# Buck_V1.net
KiCad netlist of a schematic drawn in EAGLE
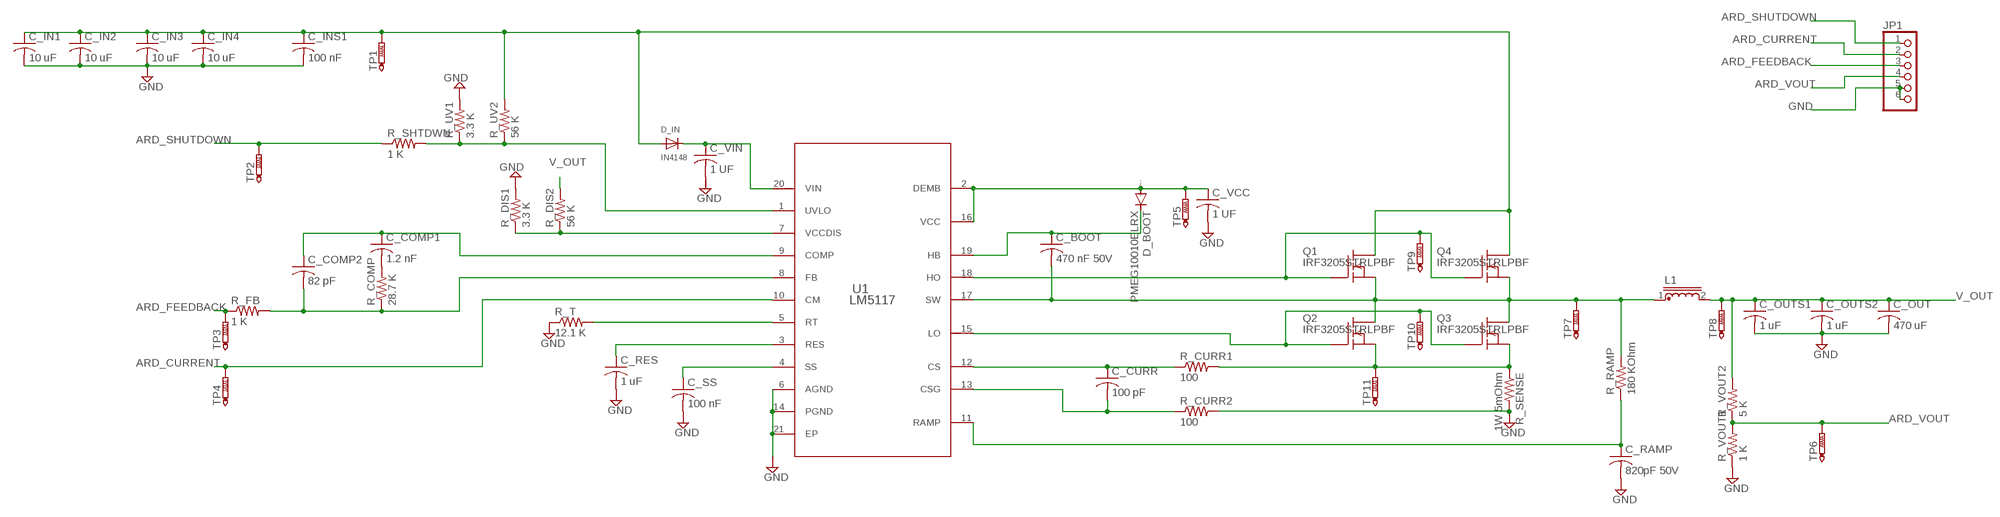
[diagram p0: schematic, sheet 1]

(export (version "E")
  (design (tool "Eeschema 10.0.6"))
  (components
    (comp (ref "C_BOOT")
      (value "470 nF 50V")
      (footprint "eagle-import:C0603")
      (libsource (lib "eagle-import") (part "rcl_334_C-USC0603"))
    )
    (comp (ref "C_COMP1")
      (value "1.2 nF")
      (footprint "eagle-import:C0603")
      (libsource (lib "eagle-import") (part "C-USC0603"))
    )
    (comp (ref "C_COMP2")
      (value "82 pF")
      (footprint "eagle-import:C0603")
      (libsource (lib "eagle-import") (part "C-USC0603"))
    )
    (comp (ref "C_CURR")
      (value "100 pF")
      (footprint "eagle-import:C0603")
      (libsource (lib "eagle-import") (part "C-USC0603"))
    )
    (comp (ref "C_IN1")
      (value "10 uF")
      (footprint "eagle-import:C1206")
      (libsource (lib "eagle-import") (part "C-USC1206"))
    )
    (comp (ref "C_IN2")
      (value "10 uF")
      (footprint "eagle-import:C1206")
      (libsource (lib "eagle-import") (part "C-USC1206"))
    )
    (comp (ref "C_IN3")
      (value "10 uF")
      (footprint "eagle-import:C1206")
      (libsource (lib "eagle-import") (part "C-USC1206"))
    )
    (comp (ref "C_IN4")
      (value "10 uF")
      (footprint "eagle-import:C1206")
      (fields (field (name "SPICEPREFIX") "C"))
      (libsource (lib "eagle-import") (part "C-USC1206"))
    )
    (comp (ref "C_INS1")
      (value "100 nF")
      (footprint "eagle-import:C0603")
      (libsource (lib "eagle-import") (part "C-USC0603"))
    )
    (comp (ref "C_OUT")
      (value "470 uF")
      (footprint "eagle-import:CAP_PANASONIC_H13")
      (libsource (lib "eagle-import") (part "CAP_PANASONIC_H13"))
    )
    (comp (ref "C_OUTS1")
      (value "1 uF")
      (footprint "eagle-import:C0805")
      (libsource (lib "eagle-import") (part "rcl_334_C-USC0805"))
    )
    (comp (ref "C_OUTS2")
      (value "1 uF")
      (footprint "eagle-import:C0805")
      (libsource (lib "eagle-import") (part "rcl_334_C-USC0805"))
    )
    (comp (ref "C_RAMP")
      (value "820pF 50V")
      (footprint "eagle-import:C0603")
      (libsource (lib "eagle-import") (part "rcl_334_C-USC0603"))
    )
    (comp (ref "C_RES")
      (value "1 uF")
      (footprint "eagle-import:C0603")
      (libsource (lib "eagle-import") (part "C-USC0603"))
    )
    (comp (ref "C_SS")
      (value "100 nF")
      (footprint "eagle-import:C0603")
      (libsource (lib "eagle-import") (part "C-USC0603"))
    )
    (comp (ref "C_VCC")
      (value "1 UF")
      (footprint "eagle-import:C0603")
      (libsource (lib "eagle-import") (part "rcl_334_C-USC0603"))
    )
    (comp (ref "C_VIN")
      (value "1 UF")
      (footprint "eagle-import:C0603")
      (libsource (lib "eagle-import") (part "rcl_334_C-USC0603"))
    )
    (comp (ref "D_BOOT")
      (value "PMEG10010ELRX")
      (footprint "eagle-import:SOD123")
      (libsource (lib "eagle-import") (part "DIODE-SOD123"))
    )
    (comp (ref "D_IN")
      (value "IN4148")
      (footprint "eagle-import:SOD-123")
      (libsource (lib "eagle-import") (part "DIODESOD-123"))
    )
    (comp (ref "JP1")
      (value "PINHD-1X6")
      (footprint "eagle-import:1X06")
      (libsource (lib "eagle-import") (part "PINHD-1X6"))
    )
    (comp (ref "L1")
      (value "17.5X17.5_INDUCTOR_SMD")
      (footprint "eagle-import:17.5X17.5_INDUCTOR_SMD")
      (libsource (lib "eagle-import") (part "17.5X17.5_INDUCTOR_SMD"))
    )
    (comp (ref "Q1")
      (value "IRF3205STRLPBF")
      (footprint "eagle-import:D2PAK")
      (libsource (lib "eagle-import") (part "IRF510D2PAK"))
    )
    (comp (ref "Q2")
      (value "IRF3205STRLPBF")
      (footprint "eagle-import:D2PAK")
      (libsource (lib "eagle-import") (part "IRF510D2PAK"))
    )
    (comp (ref "Q3")
      (value "IRF3205STRLPBF")
      (footprint "eagle-import:D2PAK")
      (libsource (lib "eagle-import") (part "IRF510D2PAK"))
    )
    (comp (ref "Q4")
      (value "IRF3205STRLPBF")
      (footprint "eagle-import:D2PAK")
      (libsource (lib "eagle-import") (part "IRF510D2PAK"))
    )
    (comp (ref "R_COMP")
      (value "28.7 K")
      (footprint "eagle-import:R0603")
      (libsource (lib "eagle-import") (part "R-US_R0603"))
    )
    (comp (ref "R_CURR1")
      (value "100")
      (footprint "eagle-import:R0603")
      (libsource (lib "eagle-import") (part "R-US_R0603"))
    )
    (comp (ref "R_CURR2")
      (value "100")
      (footprint "eagle-import:R0603")
      (libsource (lib "eagle-import") (part "R-US_R0603"))
    )
    (comp (ref "R_DIS1")
      (value "3.3 K")
      (footprint "eagle-import:R0603")
      (libsource (lib "eagle-import") (part "R-US_R0603"))
    )
    (comp (ref "R_DIS2")
      (value "56 K")
      (footprint "eagle-import:R0603")
      (libsource (lib "eagle-import") (part "R-US_R0603"))
    )
    (comp (ref "R_FB")
      (value "1 K")
      (footprint "eagle-import:R0603")
      (libsource (lib "eagle-import") (part "R-US_R0603"))
    )
    (comp (ref "R_RAMP")
      (value "180 KOhm")
      (footprint "eagle-import:R0603")
      (libsource (lib "eagle-import") (part "rcl_334_R-US_R0603"))
    )
    (comp (ref "R_SENSE")
      (value "1W 5mOhm")
      (footprint "eagle-import:R2512")
      (libsource (lib "eagle-import") (part "rcl_334_R-US_R2512"))
    )
    (comp (ref "R_SHTDWN")
      (value "1 K")
      (footprint "eagle-import:R0603")
      (libsource (lib "eagle-import") (part "R-US_R0603"))
    )
    (comp (ref "R_T")
      (value "12.1 K")
      (footprint "eagle-import:R0603")
      (libsource (lib "eagle-import") (part "R-US_R0603"))
    )
    (comp (ref "R_UV1")
      (value "3.3 K")
      (footprint "eagle-import:R0603")
      (libsource (lib "eagle-import") (part "R-US_R0603"))
    )
    (comp (ref "R_UV2")
      (value "56 K")
      (footprint "eagle-import:R0603")
      (libsource (lib "eagle-import") (part "R-US_R0603"))
    )
    (comp (ref "R_VOUT1")
      (value "1 K")
      (footprint "eagle-import:R0603")
      (libsource (lib "eagle-import") (part "R-US_R0603"))
    )
    (comp (ref "R_VOUT2")
      (value "5 K")
      (footprint "eagle-import:R0603")
      (libsource (lib "eagle-import") (part "R-US_R0603"))
    )
    (comp (ref "TP1")
      (value "PTR1TP20R")
      (footprint "eagle-import:TP20R")
      (libsource (lib "eagle-import") (part "PTR1TP20R"))
    )
    (comp (ref "TP2")
      (value "PTR1TP20R")
      (footprint "eagle-import:TP20R")
      (libsource (lib "eagle-import") (part "PTR1TP20R"))
    )
    (comp (ref "TP3")
      (value "PTR1TP20R")
      (footprint "eagle-import:TP20R")
      (libsource (lib "eagle-import") (part "PTR1TP20R"))
    )
    (comp (ref "TP4")
      (value "PTR1TP20R")
      (footprint "eagle-import:TP20R")
      (libsource (lib "eagle-import") (part "PTR1TP20R"))
    )
    (comp (ref "TP5")
      (value "PTR1TP20R")
      (footprint "eagle-import:TP20R")
      (libsource (lib "eagle-import") (part "PTR1TP20R"))
    )
    (comp (ref "TP6")
      (value "PTR1TP20R")
      (footprint "eagle-import:TP20R")
      (libsource (lib "eagle-import") (part "PTR1TP20R"))
    )
    (comp (ref "TP7")
      (value "PTR1TP20R")
      (footprint "eagle-import:TP20R")
      (libsource (lib "eagle-import") (part "PTR1TP20R"))
    )
    (comp (ref "TP8")
      (value "PTR1TP20R")
      (footprint "eagle-import:TP20R")
      (libsource (lib "eagle-import") (part "PTR1TP20R"))
    )
    (comp (ref "TP9")
      (value "PTR1TP20R")
      (footprint "eagle-import:TP20R")
      (libsource (lib "eagle-import") (part "PTR1TP20R"))
    )
    (comp (ref "TP10")
      (value "PTR1TP20R")
      (footprint "eagle-import:TP20R")
      (libsource (lib "eagle-import") (part "PTR1TP20R"))
    )
    (comp (ref "TP11")
      (value "PTR1TP20R")
      (footprint "eagle-import:TP20R")
      (libsource (lib "eagle-import") (part "PTR1TP20R"))
    )
    (comp (ref "U1")
      (value "LM5117")
      (footprint "eagle-import:PWP0020A")
      (fields (field (name "MANUFACTURER") "Texas Instruments") (field (name "PARTNUMBER") "LM5117PMHXNOPB"))
      (libsource (lib "eagle-import") (part "LM5117PMHX/NOPB"))
    )
  )
  (nets
    (net (code "1") (name "/ARD_CURRENT") (class "Default")
      (node (ref "JP1") (pin "2") (pinfunction "2_2") (pintype "passive"))
      (node (ref "TP4") (pin "TP") (pinfunction "TP_TP") (pintype "input"))
      (node (ref "U1") (pin "10") (pinfunction "CM_10") (pintype "output"))
    )
    (net (code "2") (name "/ARD_FEEDBACK") (class "Default")
      (node (ref "JP1") (pin "3") (pinfunction "3_3") (pintype "passive"))
      (node (ref "R_FB") (pin "1") (pinfunction "1_1") (pintype "passive"))
      (node (ref "TP3") (pin "TP") (pinfunction "TP_TP") (pintype "input"))
    )
    (net (code "3") (name "/ARD_SHUTDOWN") (class "Default")
      (node (ref "JP1") (pin "1") (pinfunction "1_1") (pintype "passive"))
      (node (ref "R_SHTDWN") (pin "1") (pinfunction "1_1") (pintype "passive"))
      (node (ref "TP2") (pin "TP") (pinfunction "TP_TP") (pintype "input"))
    )
    (net (code "4") (name "/ARD_VOUT") (class "Default")
      (node (ref "JP1") (pin "4") (pinfunction "4_4") (pintype "passive"))
      (node (ref "R_VOUT1") (pin "2") (pinfunction "2_2") (pintype "passive"))
      (node (ref "R_VOUT2") (pin "1") (pinfunction "1_1") (pintype "passive"))
      (node (ref "TP6") (pin "TP") (pinfunction "TP_TP") (pintype "input"))
    )
    (net (code "5") (name "/V_OUT") (class "Default")
      (node (ref "C_OUT") (pin "P$2") (pinfunction "2_P$2") (pintype "passive"))
      (node (ref "C_OUTS1") (pin "1") (pinfunction "1_1") (pintype "passive"))
      (node (ref "C_OUTS2") (pin "1") (pinfunction "1_1") (pintype "passive"))
      (node (ref "L1") (pin "2") (pinfunction "2_2") (pintype "passive"))
      (node (ref "R_DIS2") (pin "2") (pinfunction "2_2") (pintype "passive"))
      (node (ref "R_VOUT2") (pin "2") (pinfunction "2_2") (pintype "passive"))
      (node (ref "TP8") (pin "TP") (pinfunction "TP_TP") (pintype "input"))
    )
    (net (code "6") (name "GND") (class "Default")
      (node (ref "C_IN1") (pin "2") (pinfunction "2_2") (pintype "passive"))
      (node (ref "C_IN2") (pin "2") (pinfunction "2_2") (pintype "passive"))
      (node (ref "C_IN3") (pin "2") (pinfunction "2_2") (pintype "passive"))
      (node (ref "C_IN4") (pin "2") (pinfunction "2_2") (pintype "passive"))
      (node (ref "C_INS1") (pin "2") (pinfunction "2_2") (pintype "passive"))
      (node (ref "C_OUT") (pin "P$1") (pinfunction "1_P$1") (pintype "passive"))
      (node (ref "C_OUTS1") (pin "2") (pinfunction "2_2") (pintype "passive"))
      (node (ref "C_OUTS2") (pin "2") (pinfunction "2_2") (pintype "passive"))
      (node (ref "C_RAMP") (pin "2") (pinfunction "2_2") (pintype "passive"))
      (node (ref "C_RES") (pin "2") (pinfunction "2_2") (pintype "passive"))
      (node (ref "C_SS") (pin "2") (pinfunction "2_2") (pintype "passive"))
      (node (ref "C_VCC") (pin "2") (pinfunction "2_2") (pintype "passive"))
      (node (ref "C_VIN") (pin "2") (pinfunction "2_2") (pintype "passive"))
      (node (ref "JP1") (pin "5") (pinfunction "5_5") (pintype "passive"))
      (node (ref "JP1") (pin "6") (pinfunction "6_6") (pintype "passive"))
      (node (ref "R_CURR2") (pin "2") (pinfunction "2_2") (pintype "passive"))
      (node (ref "R_DIS1") (pin "2") (pinfunction "2_2") (pintype "passive"))
      (node (ref "R_SENSE") (pin "2") (pinfunction "2_2") (pintype "passive"))
      (node (ref "R_T") (pin "1") (pinfunction "1_1") (pintype "passive"))
      (node (ref "R_UV1") (pin "2") (pinfunction "2_2") (pintype "passive"))
      (node (ref "R_VOUT1") (pin "1") (pinfunction "1_1") (pintype "passive"))
      (node (ref "U1") (pin "14") (pinfunction "PGND_14") (pintype "power_in"))
      (node (ref "U1") (pin "21") (pinfunction "EP_21") (pintype "passive"))
      (node (ref "U1") (pin "6") (pinfunction "AGND_6") (pintype "power_in"))
    )
    (net (code "7") (name "Net-(C_COMP1-Pad2)") (class "Default")
      (node (ref "C_COMP1") (pin "2") (pinfunction "2_2") (pintype "passive"))
      (node (ref "R_COMP") (pin "2") (pinfunction "2_2") (pintype "passive"))
    )
    (net (code "8") (name "Net-(Q1-D)") (class "Default")
      (node (ref "C_IN1") (pin "1") (pinfunction "1_1") (pintype "passive"))
      (node (ref "C_IN2") (pin "1") (pinfunction "1_1") (pintype "passive"))
      (node (ref "C_IN3") (pin "1") (pinfunction "1_1") (pintype "passive"))
      (node (ref "C_IN4") (pin "1") (pinfunction "1_1") (pintype "passive"))
      (node (ref "C_INS1") (pin "1") (pinfunction "1_1") (pintype "passive"))
      (node (ref "D_IN") (pin "A") (pinfunction "A_A") (pintype "passive"))
      (node (ref "Q1") (pin "2") (pinfunction "D_2") (pintype "passive"))
      (node (ref "Q4") (pin "2") (pinfunction "D_2") (pintype "passive"))
      (node (ref "R_UV2") (pin "2") (pinfunction "2_2") (pintype "passive"))
      (node (ref "TP1") (pin "TP") (pinfunction "TP_TP") (pintype "input"))
    )
    (net (code "9") (name "Net-(Q1-G)") (class "Default")
      (node (ref "Q1") (pin "1") (pinfunction "G_1") (pintype "passive"))
      (node (ref "Q4") (pin "1") (pinfunction "G_1") (pintype "passive"))
      (node (ref "TP9") (pin "TP") (pinfunction "TP_TP") (pintype "input"))
      (node (ref "U1") (pin "18") (pinfunction "HO_18") (pintype "output"))
    )
    (net (code "10") (name "Net-(Q1-S)") (class "Default")
      (node (ref "C_BOOT") (pin "2") (pinfunction "2_2") (pintype "passive"))
      (node (ref "L1") (pin "1") (pinfunction "1_1") (pintype "passive"))
      (node (ref "Q1") (pin "3") (pinfunction "S_3") (pintype "passive"))
      (node (ref "Q2") (pin "2") (pinfunction "D_2") (pintype "passive"))
      (node (ref "Q3") (pin "2") (pinfunction "D_2") (pintype "passive"))
      (node (ref "Q4") (pin "3") (pinfunction "S_3") (pintype "passive"))
      (node (ref "R_RAMP") (pin "2") (pinfunction "2_2") (pintype "passive"))
      (node (ref "TP7") (pin "TP") (pinfunction "TP_TP") (pintype "input"))
      (node (ref "U1") (pin "17") (pinfunction "SW_17") (pintype "power_in"))
    )
    (net (code "11") (name "Net-(Q2-G)") (class "Default")
      (node (ref "Q2") (pin "1") (pinfunction "G_1") (pintype "passive"))
      (node (ref "Q3") (pin "1") (pinfunction "G_1") (pintype "passive"))
      (node (ref "TP10") (pin "TP") (pinfunction "TP_TP") (pintype "input"))
      (node (ref "U1") (pin "15") (pinfunction "LO_15") (pintype "output"))
    )
    (net (code "12") (name "Net-(Q2-S)") (class "Default")
      (node (ref "Q2") (pin "3") (pinfunction "S_3") (pintype "passive"))
      (node (ref "Q3") (pin "3") (pinfunction "S_3") (pintype "passive"))
      (node (ref "R_CURR1") (pin "2") (pinfunction "2_2") (pintype "passive"))
      (node (ref "R_SENSE") (pin "1") (pinfunction "1_1") (pintype "passive"))
      (node (ref "TP11") (pin "TP") (pinfunction "TP_TP") (pintype "input"))
    )
    (net (code "13") (name "Net-(U1-COMP)") (class "Default")
      (node (ref "C_COMP1") (pin "1") (pinfunction "1_1") (pintype "passive"))
      (node (ref "C_COMP2") (pin "1") (pinfunction "1_1") (pintype "passive"))
      (node (ref "U1") (pin "9") (pinfunction "COMP_9") (pintype "output"))
    )
    (net (code "14") (name "Net-(U1-CS)") (class "Default")
      (node (ref "C_CURR") (pin "1") (pinfunction "1_1") (pintype "passive"))
      (node (ref "R_CURR1") (pin "1") (pinfunction "1_1") (pintype "passive"))
      (node (ref "U1") (pin "12") (pinfunction "CS_12") (pintype "input"))
    )
    (net (code "15") (name "Net-(U1-CSG)") (class "Default")
      (node (ref "C_CURR") (pin "2") (pinfunction "2_2") (pintype "passive"))
      (node (ref "R_CURR2") (pin "1") (pinfunction "1_1") (pintype "passive"))
      (node (ref "U1") (pin "13") (pinfunction "CSG_13") (pintype "input"))
    )
    (net (code "16") (name "Net-(U1-DEMB)") (class "Default")
      (node (ref "C_VCC") (pin "1") (pinfunction "1_1") (pintype "passive"))
      (node (ref "D_BOOT") (pin "A") (pinfunction "A_A") (pintype "passive"))
      (node (ref "TP5") (pin "TP") (pinfunction "TP_TP") (pintype "input"))
      (node (ref "U1") (pin "16") (pinfunction "VCC_16") (pintype "power_in"))
      (node (ref "U1") (pin "2") (pinfunction "DEMB_2") (pintype "passive"))
    )
    (net (code "17") (name "Net-(U1-FB)") (class "Default")
      (node (ref "C_COMP2") (pin "2") (pinfunction "2_2") (pintype "passive"))
      (node (ref "R_COMP") (pin "1") (pinfunction "1_1") (pintype "passive"))
      (node (ref "R_FB") (pin "2") (pinfunction "2_2") (pintype "passive"))
      (node (ref "U1") (pin "8") (pinfunction "FB_8") (pintype "input"))
    )
    (net (code "18") (name "Net-(U1-HB)") (class "Default")
      (node (ref "C_BOOT") (pin "1") (pinfunction "1_1") (pintype "passive"))
      (node (ref "D_BOOT") (pin "C") (pinfunction "C_C") (pintype "passive"))
      (node (ref "U1") (pin "19") (pinfunction "HB_19") (pintype "output"))
    )
    (net (code "19") (name "Net-(U1-RAMP)") (class "Default")
      (node (ref "C_RAMP") (pin "1") (pinfunction "1_1") (pintype "passive"))
      (node (ref "R_RAMP") (pin "1") (pinfunction "1_1") (pintype "passive"))
      (node (ref "U1") (pin "11") (pinfunction "RAMP_11") (pintype "input"))
    )
    (net (code "20") (name "Net-(U1-RES)") (class "Default")
      (node (ref "C_RES") (pin "1") (pinfunction "1_1") (pintype "passive"))
      (node (ref "U1") (pin "3") (pinfunction "RES_3") (pintype "input"))
    )
    (net (code "21") (name "Net-(U1-RT)") (class "Default")
      (node (ref "R_T") (pin "2") (pinfunction "2_2") (pintype "passive"))
      (node (ref "U1") (pin "5") (pinfunction "RT_5") (pintype "input"))
    )
    (net (code "22") (name "Net-(U1-SS)") (class "Default")
      (node (ref "C_SS") (pin "1") (pinfunction "1_1") (pintype "passive"))
      (node (ref "U1") (pin "4") (pinfunction "SS_4") (pintype "input"))
    )
    (net (code "23") (name "Net-(U1-UVLO)") (class "Default")
      (node (ref "R_SHTDWN") (pin "2") (pinfunction "2_2") (pintype "passive"))
      (node (ref "R_UV1") (pin "1") (pinfunction "1_1") (pintype "passive"))
      (node (ref "R_UV2") (pin "1") (pinfunction "1_1") (pintype "passive"))
      (node (ref "U1") (pin "1") (pinfunction "UVLO_1") (pintype "input"))
    )
    (net (code "24") (name "Net-(U1-VCCDIS)") (class "Default")
      (node (ref "R_DIS1") (pin "1") (pinfunction "1_1") (pintype "passive"))
      (node (ref "R_DIS2") (pin "1") (pinfunction "1_1") (pintype "passive"))
      (node (ref "U1") (pin "7") (pinfunction "VCCDIS_7") (pintype "passive"))
    )
    (net (code "25") (name "Net-(U1-VIN)") (class "Default")
      (node (ref "C_VIN") (pin "1") (pinfunction "1_1") (pintype "passive"))
      (node (ref "D_IN") (pin "C") (pinfunction "C_C") (pintype "passive"))
      (node (ref "U1") (pin "20") (pinfunction "VIN_20") (pintype "power_in"))
    )
  )
)
